# untitled.net
KiCad netlist of a schematic drawn in EAGLE
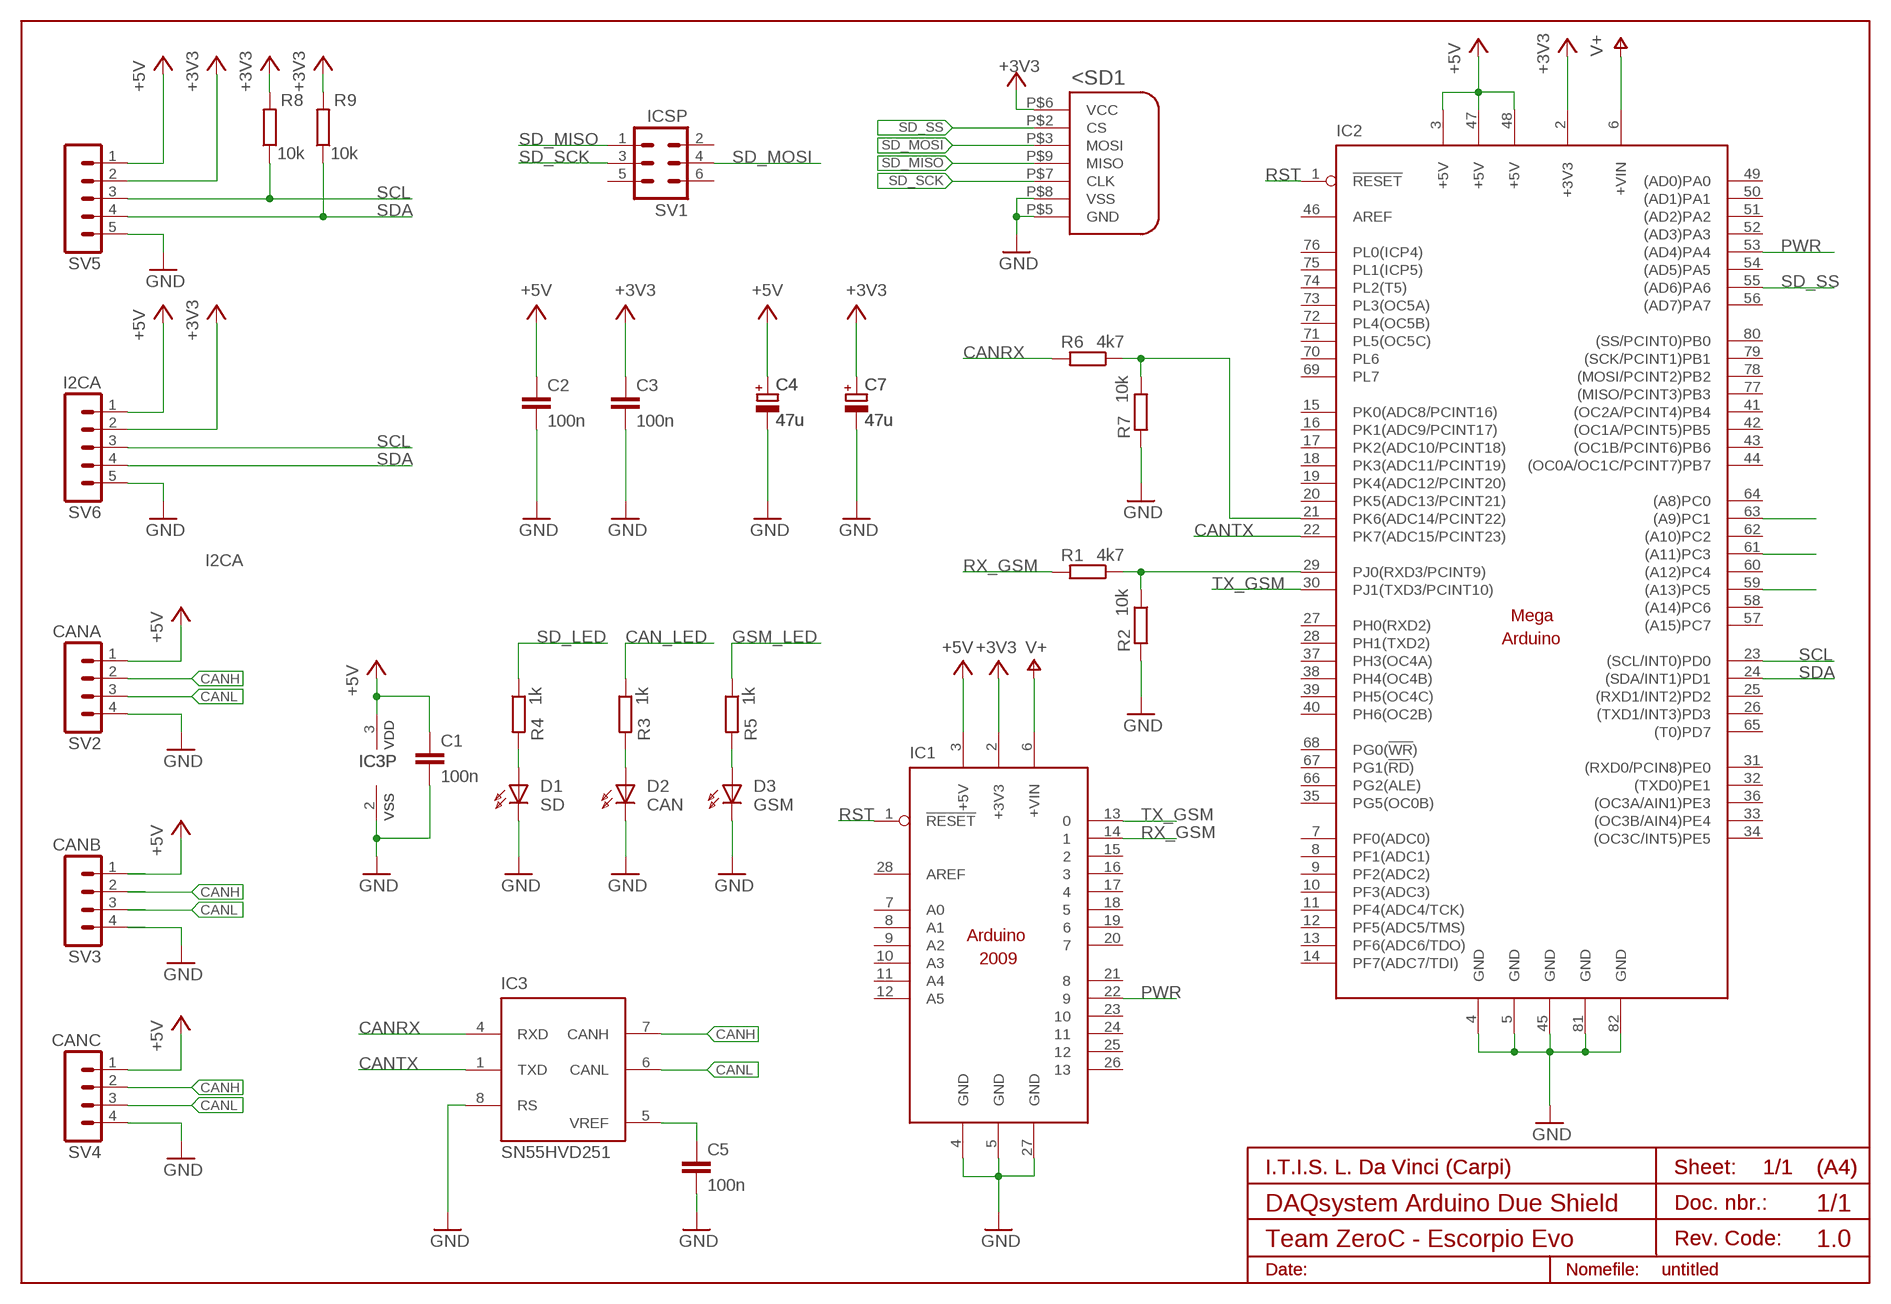
[diagram p0: schematic, sheet 1]

(export (version "E")
  (design (tool "Eeschema 10.0.6"))
  (components
    (comp (ref "C1")
      (value "100n")
      (footprint "eagle-import:C3225")
      (libsource (lib "eagle-import") (part "C-EUC3225"))
    )
    (comp (ref "C2")
      (value "100n")
      (footprint "eagle-import:C3225")
      (libsource (lib "eagle-import") (part "C-EUC3225"))
    )
    (comp (ref "C3")
      (value "100n")
      (footprint "eagle-import:C3225")
      (libsource (lib "eagle-import") (part "C-EUC3225"))
    )
    (comp (ref "C4")
      (value "47u")
      (footprint "eagle-import:E-01")
      (libsource (lib "eagle-import") (part "C_POL_01"))
    )
    (comp (ref "C5")
      (value "100n")
      (footprint "eagle-import:C3225")
      (libsource (lib "eagle-import") (part "C-EUC3225"))
    )
    (comp (ref "C7")
      (value "47u")
      (footprint "eagle-import:E-01")
      (libsource (lib "eagle-import") (part "C_POL_01"))
    )
    (comp (ref "D1")
      (value "SD")
      (footprint "eagle-import:LED5MM")
      (libsource (lib "eagle-import") (part "LED5MM"))
    )
    (comp (ref "D2")
      (value "CAN")
      (footprint "eagle-import:LED5MM")
      (libsource (lib "eagle-import") (part "LED5MM"))
    )
    (comp (ref "D3")
      (value "GSM")
      (footprint "eagle-import:LED5MM")
      (libsource (lib "eagle-import") (part "LED5MM"))
    )
    (comp (ref "IC1")
      (value "ARDUINO2009_10")
      (footprint "eagle-import:ARDUINO2009")
      (libsource (lib "eagle-import") (part "ARDUINO2009_10"))
    )
    (comp (ref "IC2")
      (value "MEGAARDUINO_1")
      (footprint "eagle-import:MEGA_ARDUINO")
      (libsource (lib "eagle-import") (part "MEGAARDUINO_1"))
    )
    (comp (ref "IC3")
      (value "SN55HVD251")
      (footprint "eagle-import:DIL8")
      (libsource (lib "eagle-import") (part "SN55HVD251"))
    )
    (comp (ref "R1")
      (value "4k7")
      (footprint "eagle-import:M1206")
      (libsource (lib "eagle-import") (part "R-EU_M1206"))
    )
    (comp (ref "R2")
      (value "10k")
      (footprint "eagle-import:M1206")
      (libsource (lib "eagle-import") (part "R-EU_M1206"))
    )
    (comp (ref "R3")
      (value "1k")
      (footprint "eagle-import:M1206")
      (libsource (lib "eagle-import") (part "R-EU_M1206"))
    )
    (comp (ref "R4")
      (value "1k")
      (footprint "eagle-import:M1206")
      (libsource (lib "eagle-import") (part "R-EU_M1206"))
    )
    (comp (ref "R5")
      (value "1k")
      (footprint "eagle-import:M1206")
      (libsource (lib "eagle-import") (part "R-EU_M1206"))
    )
    (comp (ref "R6")
      (value "4k7")
      (footprint "eagle-import:M1206")
      (libsource (lib "eagle-import") (part "R-EU_M1206"))
    )
    (comp (ref "R7")
      (value "10k")
      (footprint "eagle-import:M1206")
      (libsource (lib "eagle-import") (part "R-EU_M1206"))
    )
    (comp (ref "R8")
      (value "10k")
      (footprint "eagle-import:M1206")
      (libsource (lib "eagle-import") (part "R-EU_M1206"))
    )
    (comp (ref "R9")
      (value "10k")
      (footprint "eagle-import:M1206")
      (libsource (lib "eagle-import") (part "R-EU_M1206"))
    )
    (comp (ref "SV1")
      (value "ICSP")
      (footprint "eagle-import:MA03-2")
      (libsource (lib "eagle-import") (part "MA03-2"))
    )
    (comp (ref "SV2")
      (value "CANA")
      (footprint "eagle-import:MA04-1")
      (libsource (lib "eagle-import") (part "MA04-1"))
    )
    (comp (ref "SV3")
      (value "CANB")
      (footprint "eagle-import:MA04-1")
      (fields (field (name "OC_FARNELL") "unknown") (field (name "OC_NEWARK") "unknown"))
      (libsource (lib "eagle-import") (part "MA04-1"))
    )
    (comp (ref "SV4")
      (value "CANC")
      (footprint "eagle-import:MA04-1")
      (fields (field (name "OC_FARNELL") "unknown") (field (name "OC_NEWARK") "unknown"))
      (libsource (lib "eagle-import") (part "MA04-1"))
    )
    (comp (ref "SV5")
      (value "I2CA")
      (footprint "eagle-import:MA05-1")
      (libsource (lib "eagle-import") (part "MA05-1"))
    )
    (comp (ref "SV6")
      (value "I2CA")
      (footprint "eagle-import:MA05-1")
      (libsource (lib "eagle-import") (part "MA05-1"))
    )
    (comp (ref "U$2")
      (value "SD_CARD")
      (footprint "eagle-import:SD")
      (libsource (lib "eagle-import") (part "SD_CARD"))
    )
  )
  (nets
    (net (code "1") (name "+3V3") (class "Default")
      (node (ref "C3") (pin "1") (pinfunction "1_1") (pintype "passive"))
      (node (ref "C7") (pin "+") (pinfunction "+_+") (pintype "passive"))
      (node (ref "IC1") (pin "2") (pinfunction "+3V3_2") (pintype "power_in"))
      (node (ref "IC2") (pin "2") (pinfunction "+3V3_2") (pintype "power_in"))
      (node (ref "R8") (pin "2") (pinfunction "2_2") (pintype "passive"))
      (node (ref "R9") (pin "2") (pinfunction "2_2") (pintype "passive"))
      (node (ref "SV5") (pin "2") (pinfunction "2_2") (pintype "passive"))
      (node (ref "SV6") (pin "2") (pinfunction "2_2") (pintype "passive"))
      (node (ref "U$2") (pin "P$6") (pinfunction "VCC_P$6") (pintype "bidirectional"))
    )
    (net (code "2") (name "+5V") (class "Default")
      (node (ref "C1") (pin "1") (pinfunction "1_1") (pintype "passive"))
      (node (ref "C2") (pin "1") (pinfunction "1_1") (pintype "passive"))
      (node (ref "C4") (pin "+") (pinfunction "+_+") (pintype "passive"))
      (node (ref "IC1") (pin "3") (pinfunction "+5V_3") (pintype "power_in"))
      (node (ref "IC2") (pin "3") (pinfunction "+5V_3") (pintype "power_in"))
      (node (ref "IC2") (pin "47") (pinfunction "+5V_47") (pintype "power_in"))
      (node (ref "IC2") (pin "48") (pinfunction "+5V_48") (pintype "power_in"))
      (node (ref "IC3") (pin "3") (pinfunction "VDD_3") (pintype "power_in"))
      (node (ref "SV2") (pin "1") (pinfunction "1_1") (pintype "passive"))
      (node (ref "SV3") (pin "1") (pinfunction "1_1") (pintype "passive"))
      (node (ref "SV4") (pin "1") (pinfunction "1_1") (pintype "passive"))
      (node (ref "SV5") (pin "1") (pinfunction "1_1") (pintype "passive"))
      (node (ref "SV6") (pin "1") (pinfunction "1_1") (pintype "passive"))
    )
    (net (code "3") (name "/CANH") (class "Default")
      (node (ref "IC3") (pin "7") (pinfunction "CANH_7") (pintype "bidirectional"))
      (node (ref "SV2") (pin "2") (pinfunction "2_2") (pintype "passive"))
      (node (ref "SV3") (pin "2") (pinfunction "2_2") (pintype "passive"))
      (node (ref "SV4") (pin "2") (pinfunction "2_2") (pintype "passive"))
    )
    (net (code "4") (name "/CANL") (class "Default")
      (node (ref "IC3") (pin "6") (pinfunction "CANL_6") (pintype "bidirectional"))
      (node (ref "SV2") (pin "3") (pinfunction "3_3") (pintype "passive"))
      (node (ref "SV3") (pin "3") (pinfunction "3_3") (pintype "passive"))
      (node (ref "SV4") (pin "3") (pinfunction "3_3") (pintype "passive"))
    )
    (net (code "5") (name "/CANRX") (class "Default")
      (node (ref "IC3") (pin "4") (pinfunction "RXD_4") (pintype "output"))
      (node (ref "R6") (pin "2") (pinfunction "2_2") (pintype "passive"))
    )
    (net (code "6") (name "/CANTX") (class "Default")
      (node (ref "IC2") (pin "22") (pinfunction "PK7(ADC15/PCINT23)_22") (pintype "bidirectional"))
      (node (ref "IC3") (pin "1") (pinfunction "TXD_1") (pintype "input"))
    )
    (net (code "7") (name "/CAN_LED") (class "Default")
      (node (ref "IC2") (pin "63") (pinfunction "(A9)PC1_63") (pintype "bidirectional"))
      (node (ref "R3") (pin "1") (pinfunction "1_1") (pintype "passive"))
    )
    (net (code "8") (name "/GSM_LED") (class "Default")
      (node (ref "IC2") (pin "61") (pinfunction "(A11)PC3_61") (pintype "bidirectional"))
      (node (ref "R5") (pin "1") (pinfunction "1_1") (pintype "passive"))
    )
    (net (code "9") (name "/PWR") (class "Default")
      (node (ref "IC1") (pin "22") (pinfunction "9_22") (pintype "bidirectional"))
      (node (ref "IC2") (pin "53") (pinfunction "(AD4)PA4_53") (pintype "bidirectional"))
    )
    (net (code "10") (name "/RST") (class "Default")
      (node (ref "IC1") (pin "1") (pinfunction "~{RESET}_1") (pintype "bidirectional"))
      (node (ref "IC2") (pin "1") (pinfunction "~{RESET}_1") (pintype "bidirectional"))
    )
    (net (code "11") (name "/RX_GSM") (class "Default")
      (node (ref "IC1") (pin "14") (pinfunction "1_14") (pintype "bidirectional"))
      (node (ref "R1") (pin "2") (pinfunction "2_2") (pintype "passive"))
    )
    (net (code "12") (name "/SCL") (class "Default")
      (node (ref "IC2") (pin "23") (pinfunction "(SCL/INT0)PD0_23") (pintype "bidirectional"))
      (node (ref "R8") (pin "1") (pinfunction "1_1") (pintype "passive"))
      (node (ref "SV5") (pin "3") (pinfunction "3_3") (pintype "passive"))
      (node (ref "SV6") (pin "3") (pinfunction "3_3") (pintype "passive"))
    )
    (net (code "13") (name "/SDA") (class "Default")
      (node (ref "IC2") (pin "24") (pinfunction "(SDA/INT1)PD1_24") (pintype "bidirectional"))
      (node (ref "R9") (pin "1") (pinfunction "1_1") (pintype "passive"))
      (node (ref "SV5") (pin "4") (pinfunction "4_4") (pintype "passive"))
      (node (ref "SV6") (pin "4") (pinfunction "4_4") (pintype "passive"))
    )
    (net (code "14") (name "/SD_LED") (class "Default")
      (node (ref "IC2") (pin "59") (pinfunction "(A13)PC5_59") (pintype "bidirectional"))
      (node (ref "R4") (pin "1") (pinfunction "1_1") (pintype "passive"))
    )
    (net (code "15") (name "/SD_MISO") (class "Default")
      (node (ref "SV1") (pin "1") (pinfunction "1_1") (pintype "passive"))
      (node (ref "U$2") (pin "P$9") (pinfunction "MISO_P$9") (pintype "bidirectional"))
    )
    (net (code "16") (name "/SD_MOSI") (class "Default")
      (node (ref "SV1") (pin "4") (pinfunction "4_4") (pintype "passive"))
      (node (ref "U$2") (pin "P$3") (pinfunction "MOSI_P$3") (pintype "bidirectional"))
    )
    (net (code "17") (name "/SD_SCK") (class "Default")
      (node (ref "SV1") (pin "3") (pinfunction "3_3") (pintype "passive"))
      (node (ref "U$2") (pin "P$7") (pinfunction "CLK_P$7") (pintype "bidirectional"))
    )
    (net (code "18") (name "/SD_SS") (class "Default")
      (node (ref "IC2") (pin "55") (pinfunction "(AD6)PA6_55") (pintype "bidirectional"))
      (node (ref "U$2") (pin "P$2") (pinfunction "CS_P$2") (pintype "bidirectional"))
    )
    (net (code "19") (name "/TX_GSM") (class "Default")
      (node (ref "IC1") (pin "13") (pinfunction "0_13") (pintype "bidirectional"))
      (node (ref "IC2") (pin "30") (pinfunction "PJ1(TXD3/PCINT10)_30") (pintype "bidirectional"))
    )
    (net (code "20") (name "GND") (class "Default")
      (node (ref "C1") (pin "2") (pinfunction "2_2") (pintype "passive"))
      (node (ref "C2") (pin "2") (pinfunction "2_2") (pintype "passive"))
      (node (ref "C3") (pin "2") (pinfunction "2_2") (pintype "passive"))
      (node (ref "C4") (pin "-") (pinfunction "-_-") (pintype "passive"))
      (node (ref "C5") (pin "2") (pinfunction "2_2") (pintype "passive"))
      (node (ref "C7") (pin "-") (pinfunction "-_-") (pintype "passive"))
      (node (ref "D1") (pin "K") (pinfunction "C_K") (pintype "passive"))
      (node (ref "D2") (pin "K") (pinfunction "C_K") (pintype "passive"))
      (node (ref "D3") (pin "K") (pinfunction "C_K") (pintype "passive"))
      (node (ref "IC1") (pin "27") (pinfunction "GND_27") (pintype "power_in"))
      (node (ref "IC1") (pin "4") (pinfunction "GND_4") (pintype "power_in"))
      (node (ref "IC1") (pin "5") (pinfunction "GND_5") (pintype "power_in"))
      (node (ref "IC2") (pin "4") (pinfunction "GND_4") (pintype "power_in"))
      (node (ref "IC2") (pin "45") (pinfunction "GND_45") (pintype "power_in"))
      (node (ref "IC2") (pin "5") (pinfunction "GND_5") (pintype "power_in"))
      (node (ref "IC2") (pin "81") (pinfunction "GND_81") (pintype "power_in"))
      (node (ref "IC2") (pin "82") (pinfunction "GND_82") (pintype "power_in"))
      (node (ref "IC3") (pin "2") (pinfunction "VSS_2") (pintype "power_in"))
      (node (ref "IC3") (pin "8") (pinfunction "RS_8") (pintype "input"))
      (node (ref "R2") (pin "2") (pinfunction "2_2") (pintype "passive"))
      (node (ref "R7") (pin "2") (pinfunction "2_2") (pintype "passive"))
      (node (ref "SV2") (pin "4") (pinfunction "4_4") (pintype "passive"))
      (node (ref "SV3") (pin "4") (pinfunction "4_4") (pintype "passive"))
      (node (ref "SV4") (pin "4") (pinfunction "4_4") (pintype "passive"))
      (node (ref "SV5") (pin "5") (pinfunction "5_5") (pintype "passive"))
      (node (ref "SV6") (pin "5") (pinfunction "5_5") (pintype "passive"))
      (node (ref "U$2") (pin "P$5") (pinfunction "GND_P$5") (pintype "bidirectional"))
      (node (ref "U$2") (pin "P$8") (pinfunction "VSS_P$8") (pintype "bidirectional"))
    )
    (net (code "21") (name "Net-(D1-PadA)") (class "Default")
      (node (ref "D1") (pin "A") (pinfunction "A_A") (pintype "passive"))
      (node (ref "R4") (pin "2") (pinfunction "2_2") (pintype "passive"))
    )
    (net (code "22") (name "Net-(D2-PadA)") (class "Default")
      (node (ref "D2") (pin "A") (pinfunction "A_A") (pintype "passive"))
      (node (ref "R3") (pin "2") (pinfunction "2_2") (pintype "passive"))
    )
    (net (code "23") (name "Net-(D3-PadA)") (class "Default")
      (node (ref "D3") (pin "A") (pinfunction "A_A") (pintype "passive"))
      (node (ref "R5") (pin "2") (pinfunction "2_2") (pintype "passive"))
    )
    (net (code "24") (name "Net-(IC2-PJ0(RXD3{slash}PCINT9))") (class "Default")
      (node (ref "IC2") (pin "29") (pinfunction "PJ0(RXD3/PCINT9)_29") (pintype "bidirectional"))
      (node (ref "R1") (pin "1") (pinfunction "1_1") (pintype "passive"))
      (node (ref "R2") (pin "1") (pinfunction "1_1") (pintype "passive"))
    )
    (net (code "25") (name "Net-(IC2-PK6(ADC14{slash}PCINT22))") (class "Default")
      (node (ref "IC2") (pin "21") (pinfunction "PK6(ADC14/PCINT22)_21") (pintype "bidirectional"))
      (node (ref "R6") (pin "1") (pinfunction "1_1") (pintype "passive"))
      (node (ref "R7") (pin "1") (pinfunction "1_1") (pintype "passive"))
    )
    (net (code "26") (name "Net-(IC3A-VREF)") (class "Default")
      (node (ref "C5") (pin "1") (pinfunction "1_1") (pintype "passive"))
      (node (ref "IC3") (pin "5") (pinfunction "VREF_5") (pintype "power_in"))
    )
    (net (code "27") (name "V+") (class "Default")
      (node (ref "IC1") (pin "6") (pinfunction "+VIN_6") (pintype "bidirectional"))
      (node (ref "IC2") (pin "6") (pinfunction "+VIN_6") (pintype "power_in"))
    )
    (net (code "28") (name "unconnected-(IC1-2-Pad15)") (class "Default")
      (node (ref "IC1") (pin "15") (pinfunction "2_15") (pintype "bidirectional"))
    )
    (net (code "29") (name "unconnected-(IC1-3-Pad16)") (class "Default")
      (node (ref "IC1") (pin "16") (pinfunction "3_16") (pintype "bidirectional"))
    )
    (net (code "30") (name "unconnected-(IC1-4-Pad17)") (class "Default")
      (node (ref "IC1") (pin "17") (pinfunction "4_17") (pintype "bidirectional"))
    )
    (net (code "31") (name "unconnected-(IC1-5-Pad18)") (class "Default")
      (node (ref "IC1") (pin "18") (pinfunction "5_18") (pintype "bidirectional"))
    )
    (net (code "32") (name "unconnected-(IC1-6-Pad19)") (class "Default")
      (node (ref "IC1") (pin "19") (pinfunction "6_19") (pintype "bidirectional"))
    )
    (net (code "33") (name "unconnected-(IC1-7-Pad20)") (class "Default")
      (node (ref "IC1") (pin "20") (pinfunction "7_20") (pintype "bidirectional"))
    )
    (net (code "34") (name "unconnected-(IC1-8-Pad21)") (class "Default")
      (node (ref "IC1") (pin "21") (pinfunction "8_21") (pintype "bidirectional"))
    )
    (net (code "35") (name "unconnected-(IC1-10-Pad23)") (class "Default")
      (node (ref "IC1") (pin "23") (pinfunction "10_23") (pintype "bidirectional"))
    )
    (net (code "36") (name "unconnected-(IC1-11-Pad24)") (class "Default")
      (node (ref "IC1") (pin "24") (pinfunction "11_24") (pintype "bidirectional"))
    )
    (net (code "37") (name "unconnected-(IC1-12-Pad25)") (class "Default")
      (node (ref "IC1") (pin "25") (pinfunction "12_25") (pintype "bidirectional"))
    )
    (net (code "38") (name "unconnected-(IC1-13-Pad26)") (class "Default")
      (node (ref "IC1") (pin "26") (pinfunction "13_26") (pintype "bidirectional"))
    )
    (net (code "39") (name "unconnected-(IC1-A0-Pad7)") (class "Default")
      (node (ref "IC1") (pin "7") (pinfunction "A0_7") (pintype "bidirectional"))
    )
    (net (code "40") (name "unconnected-(IC1-A1-Pad8)") (class "Default")
      (node (ref "IC1") (pin "8") (pinfunction "A1_8") (pintype "bidirectional"))
    )
    (net (code "41") (name "unconnected-(IC1-A2-Pad9)") (class "Default")
      (node (ref "IC1") (pin "9") (pinfunction "A2_9") (pintype "bidirectional"))
    )
    (net (code "42") (name "unconnected-(IC1-A3-Pad10)") (class "Default")
      (node (ref "IC1") (pin "10") (pinfunction "A3_10") (pintype "bidirectional"))
    )
    (net (code "43") (name "unconnected-(IC1-A4-Pad11)") (class "Default")
      (node (ref "IC1") (pin "11") (pinfunction "A4_11") (pintype "bidirectional"))
    )
    (net (code "44") (name "unconnected-(IC1-A5-Pad12)") (class "Default")
      (node (ref "IC1") (pin "12") (pinfunction "A5_12") (pintype "bidirectional"))
    )
    (net (code "45") (name "unconnected-(IC1-AREF-Pad28)") (class "Default")
      (node (ref "IC1") (pin "28") (pinfunction "AREF_28") (pintype "bidirectional"))
    )
    (net (code "46") (name "unconnected-(IC2-(A8)PC0-Pad64)") (class "Default")
      (node (ref "IC2") (pin "64") (pinfunction "(A8)PC0_64") (pintype "bidirectional"))
    )
    (net (code "47") (name "unconnected-(IC2-(A10)PC2-Pad62)") (class "Default")
      (node (ref "IC2") (pin "62") (pinfunction "(A10)PC2_62") (pintype "bidirectional"))
    )
    (net (code "48") (name "unconnected-(IC2-(A12)PC4-Pad60)") (class "Default")
      (node (ref "IC2") (pin "60") (pinfunction "(A12)PC4_60") (pintype "bidirectional"))
    )
    (net (code "49") (name "unconnected-(IC2-(A14)PC6-Pad58)") (class "Default")
      (node (ref "IC2") (pin "58") (pinfunction "(A14)PC6_58") (pintype "bidirectional"))
    )
    (net (code "50") (name "unconnected-(IC2-(A15)PC7-Pad57)") (class "Default")
      (node (ref "IC2") (pin "57") (pinfunction "(A15)PC7_57") (pintype "bidirectional"))
    )
    (net (code "51") (name "unconnected-(IC2-(AD0)PA0-Pad49)") (class "Default")
      (node (ref "IC2") (pin "49") (pinfunction "(AD0)PA0_49") (pintype "bidirectional"))
    )
    (net (code "52") (name "unconnected-(IC2-(AD1)PA1-Pad50)") (class "Default")
      (node (ref "IC2") (pin "50") (pinfunction "(AD1)PA1_50") (pintype "bidirectional"))
    )
    (net (code "53") (name "unconnected-(IC2-(AD2)PA2-Pad51)") (class "Default")
      (node (ref "IC2") (pin "51") (pinfunction "(AD2)PA2_51") (pintype "bidirectional"))
    )
    (net (code "54") (name "unconnected-(IC2-(AD3)PA3-Pad52)") (class "Default")
      (node (ref "IC2") (pin "52") (pinfunction "(AD3)PA3_52") (pintype "bidirectional"))
    )
    (net (code "55") (name "unconnected-(IC2-(AD5)PA5-Pad54)") (class "Default")
      (node (ref "IC2") (pin "54") (pinfunction "(AD5)PA5_54") (pintype "bidirectional"))
    )
    (net (code "56") (name "unconnected-(IC2-(AD7)PA7-Pad56)") (class "Default")
      (node (ref "IC2") (pin "56") (pinfunction "(AD7)PA7_56") (pintype "bidirectional"))
    )
    (net (code "57") (name "unconnected-(IC2-(MISO{slash}PCINT3)PB3-Pad77)") (class "Default")
      (node (ref "IC2") (pin "77") (pinfunction "(MISO/PCINT3)PB3_77") (pintype "bidirectional"))
    )
    (net (code "58") (name "unconnected-(IC2-(MOSI{slash}PCINT2)PB2-Pad78)") (class "Default")
      (node (ref "IC2") (pin "78") (pinfunction "(MOSI/PCINT2)PB2_78") (pintype "bidirectional"))
    )
    (net (code "59") (name "unconnected-(IC2-(OC0A{slash}OC1C{slash}PCINT7)PB7-Pad44)") (class "Default")
      (node (ref "IC2") (pin "44") (pinfunction "(OC0A/OC1C/PCINT7)PB7_44") (pintype "bidirectional"))
    )
    (net (code "60") (name "unconnected-(IC2-(OC1A{slash}PCINT5)PB5-Pad42)") (class "Default")
      (node (ref "IC2") (pin "42") (pinfunction "(OC1A/PCINT5)PB5_42") (pintype "bidirectional"))
    )
    (net (code "61") (name "unconnected-(IC2-(OC1B{slash}PCINT6)PB6-Pad43)") (class "Default")
      (node (ref "IC2") (pin "43") (pinfunction "(OC1B/PCINT6)PB6_43") (pintype "bidirectional"))
    )
    (net (code "62") (name "unconnected-(IC2-(OC2A{slash}PCINT4)PB4-Pad41)") (class "Default")
      (node (ref "IC2") (pin "41") (pinfunction "(OC2A/PCINT4)PB4_41") (pintype "bidirectional"))
    )
    (net (code "63") (name "unconnected-(IC2-(OC3A{slash}AIN1)PE3-Pad36)") (class "Default")
      (node (ref "IC2") (pin "36") (pinfunction "(OC3A/AIN1)PE3_36") (pintype "bidirectional"))
    )
    (net (code "64") (name "unconnected-(IC2-(OC3B{slash}AIN4)PE4-Pad33)") (class "Default")
      (node (ref "IC2") (pin "33") (pinfunction "(OC3B/AIN4)PE4_33") (pintype "bidirectional"))
    )
    (net (code "65") (name "unconnected-(IC2-(OC3C{slash}INT5)PE5-Pad34)") (class "Default")
      (node (ref "IC2") (pin "34") (pinfunction "(OC3C/INT5)PE5_34") (pintype "bidirectional"))
    )
    (net (code "66") (name "unconnected-(IC2-(RXD0{slash}PCIN8)PE0-Pad31)") (class "Default")
      (node (ref "IC2") (pin "31") (pinfunction "(RXD0/PCIN8)PE0_31") (pintype "bidirectional"))
    )
    (net (code "67") (name "unconnected-(IC2-(RXD1{slash}INT2)PD2-Pad25)") (class "Default")
      (node (ref "IC2") (pin "25") (pinfunction "(RXD1/INT2)PD2_25") (pintype "bidirectional"))
    )
    (net (code "68") (name "unconnected-(IC2-(SCK{slash}PCINT1)PB1-Pad79)") (class "Default")
      (node (ref "IC2") (pin "79") (pinfunction "(SCK/PCINT1)PB1_79") (pintype "bidirectional"))
    )
    (net (code "69") (name "unconnected-(IC2-(SS{slash}PCINT0)PB0-Pad80)") (class "Default")
      (node (ref "IC2") (pin "80") (pinfunction "(SS/PCINT0)PB0_80") (pintype "bidirectional"))
    )
    (net (code "70") (name "unconnected-(IC2-(T0)PD7-Pad65)") (class "Default")
      (node (ref "IC2") (pin "65") (pinfunction "(T0)PD7_65") (pintype "bidirectional"))
    )
    (net (code "71") (name "unconnected-(IC2-(TXD0)PE1-Pad32)") (class "Default")
      (node (ref "IC2") (pin "32") (pinfunction "(TXD0)PE1_32") (pintype "bidirectional"))
    )
    (net (code "72") (name "unconnected-(IC2-(TXD1{slash}INT3)PD3-Pad26)") (class "Default")
      (node (ref "IC2") (pin "26") (pinfunction "(TXD1/INT3)PD3_26") (pintype "bidirectional"))
    )
    (net (code "73") (name "unconnected-(IC2-AREF-Pad46)") (class "Default")
      (node (ref "IC2") (pin "46") (pinfunction "AREF_46") (pintype "bidirectional"))
    )
    (net (code "74") (name "unconnected-(IC2-PF0(ADC0)-Pad7)") (class "Default")
      (node (ref "IC2") (pin "7") (pinfunction "PF0(ADC0)_7") (pintype "bidirectional"))
    )
    (net (code "75") (name "unconnected-(IC2-PF1(ADC1)-Pad8)") (class "Default")
      (node (ref "IC2") (pin "8") (pinfunction "PF1(ADC1)_8") (pintype "bidirectional"))
    )
    (net (code "76") (name "unconnected-(IC2-PF2(ADC2)-Pad9)") (class "Default")
      (node (ref "IC2") (pin "9") (pinfunction "PF2(ADC2)_9") (pintype "bidirectional"))
    )
    (net (code "77") (name "unconnected-(IC2-PF3(ADC3)-Pad10)") (class "Default")
      (node (ref "IC2") (pin "10") (pinfunction "PF3(ADC3)_10") (pintype "bidirectional"))
    )
    (net (code "78") (name "unconnected-(IC2-PF4(ADC4{slash}TCK)-Pad11)") (class "Default")
      (node (ref "IC2") (pin "11") (pinfunction "PF4(ADC4/TCK)_11") (pintype "bidirectional"))
    )
    (net (code "79") (name "unconnected-(IC2-PF5(ADC5{slash}TMS)-Pad12)") (class "Default")
      (node (ref "IC2") (pin "12") (pinfunction "PF5(ADC5/TMS)_12") (pintype "bidirectional"))
    )
    (net (code "80") (name "unconnected-(IC2-PF6(ADC6{slash}TDO)-Pad13)") (class "Default")
      (node (ref "IC2") (pin "13") (pinfunction "PF6(ADC6/TDO)_13") (pintype "bidirectional"))
    )
    (net (code "81") (name "unconnected-(IC2-PF7(ADC7{slash}TDI)-Pad14)") (class "Default")
      (node (ref "IC2") (pin "14") (pinfunction "PF7(ADC7/TDI)_14") (pintype "bidirectional"))
    )
    (net (code "82") (name "unconnected-(IC2-PG0(~{WR})-Pad68)") (class "Default")
      (node (ref "IC2") (pin "68") (pinfunction "PG0(~{WR})_68") (pintype "bidirectional"))
    )
    (net (code "83") (name "unconnected-(IC2-PG1(~{RD})-Pad67)") (class "Default")
      (node (ref "IC2") (pin "67") (pinfunction "PG1(~{RD})_67") (pintype "bidirectional"))
    )
    (net (code "84") (name "unconnected-(IC2-PG2(ALE)-Pad66)") (class "Default")
      (node (ref "IC2") (pin "66") (pinfunction "PG2(ALE)_66") (pintype "bidirectional"))
    )
    (net (code "85") (name "unconnected-(IC2-PG5(OC0B)-Pad35)") (class "Default")
      (node (ref "IC2") (pin "35") (pinfunction "PG5(OC0B)_35") (pintype "bidirectional"))
    )
    (net (code "86") (name "unconnected-(IC2-PH0(RXD2)-Pad27)") (class "Default")
      (node (ref "IC2") (pin "27") (pinfunction "PH0(RXD2)_27") (pintype "bidirectional"))
    )
    (net (code "87") (name "unconnected-(IC2-PH1(TXD2)-Pad28)") (class "Default")
      (node (ref "IC2") (pin "28") (pinfunction "PH1(TXD2)_28") (pintype "bidirectional"))
    )
    (net (code "88") (name "unconnected-(IC2-PH3(OC4A)-Pad37)") (class "Default")
      (node (ref "IC2") (pin "37") (pinfunction "PH3(OC4A)_37") (pintype "bidirectional"))
    )
    (net (code "89") (name "unconnected-(IC2-PH4(OC4B)-Pad38)") (class "Default")
      (node (ref "IC2") (pin "38") (pinfunction "PH4(OC4B)_38") (pintype "bidirectional"))
    )
    (net (code "90") (name "unconnected-(IC2-PH5(OC4C)-Pad39)") (class "Default")
      (node (ref "IC2") (pin "39") (pinfunction "PH5(OC4C)_39") (pintype "bidirectional"))
    )
    (net (code "91") (name "unconnected-(IC2-PH6(OC2B)-Pad40)") (class "Default")
      (node (ref "IC2") (pin "40") (pinfunction "PH6(OC2B)_40") (pintype "bidirectional"))
    )
    (net (code "92") (name "unconnected-(IC2-PK0(ADC8{slash}PCINT16)-Pad15)") (class "Default")
      (node (ref "IC2") (pin "15") (pinfunction "PK0(ADC8/PCINT16)_15") (pintype "bidirectional"))
    )
    (net (code "93") (name "unconnected-(IC2-PK1(ADC9{slash}PCINT17)-Pad16)") (class "Default")
      (node (ref "IC2") (pin "16") (pinfunction "PK1(ADC9/PCINT17)_16") (pintype "bidirectional"))
    )
    (net (code "94") (name "unconnected-(IC2-PK2(ADC10{slash}PCINT18)-Pad17)") (class "Default")
      (node (ref "IC2") (pin "17") (pinfunction "PK2(ADC10/PCINT18)_17") (pintype "bidirectional"))
    )
    (net (code "95") (name "unconnected-(IC2-PK3(ADC11{slash}PCINT19)-Pad18)") (class "Default")
      (node (ref "IC2") (pin "18") (pinfunction "PK3(ADC11/PCINT19)_18") (pintype "bidirectional"))
    )
    (net (code "96") (name "unconnected-(IC2-PK4(ADC12{slash}PCINT20)-Pad19)") (class "Default")
      (node (ref "IC2") (pin "19") (pinfunction "PK4(ADC12/PCINT20)_19") (pintype "bidirectional"))
    )
    (net (code "97") (name "unconnected-(IC2-PK5(ADC13{slash}PCINT21)-Pad20)") (class "Default")
      (node (ref "IC2") (pin "20") (pinfunction "PK5(ADC13/PCINT21)_20") (pintype "bidirectional"))
    )
    (net (code "98") (name "unconnected-(IC2-PL0(ICP4)-Pad76)") (class "Default")
      (node (ref "IC2") (pin "76") (pinfunction "PL0(ICP4)_76") (pintype "bidirectional"))
    )
    (net (code "99") (name "unconnected-(IC2-PL1(ICP5)-Pad75)") (class "Default")
      (node (ref "IC2") (pin "75") (pinfunction "PL1(ICP5)_75") (pintype "bidirectional"))
    )
    (net (code "100") (name "unconnected-(IC2-PL2(T5)-Pad74)") (class "Default")
      (node (ref "IC2") (pin "74") (pinfunction "PL2(T5)_74") (pintype "bidirectional"))
    )
    (net (code "101") (name "unconnected-(IC2-PL3(OC5A)-Pad73)") (class "Default")
      (node (ref "IC2") (pin "73") (pinfunction "PL3(OC5A)_73") (pintype "bidirectional"))
    )
    (net (code "102") (name "unconnected-(IC2-PL4(OC5B)-Pad72)") (class "Default")
      (node (ref "IC2") (pin "72") (pinfunction "PL4(OC5B)_72") (pintype "bidirectional"))
    )
    (net (code "103") (name "unconnected-(IC2-PL5(OC5C)-Pad71)") (class "Default")
      (node (ref "IC2") (pin "71") (pinfunction "PL5(OC5C)_71") (pintype "bidirectional"))
    )
    (net (code "104") (name "unconnected-(IC2-PL6-Pad70)") (class "Default")
      (node (ref "IC2") (pin "70") (pinfunction "PL6_70") (pintype "bidirectional"))
    )
    (net (code "105") (name "unconnected-(IC2-PL7-Pad69)") (class "Default")
      (node (ref "IC2") (pin "69") (pinfunction "PL7_69") (pintype "bidirectional"))
    )
    (net (code "106") (name "unconnected-(SV1-Pad2)") (class "Default")
      (node (ref "SV1") (pin "2") (pinfunction "2_2") (pintype "passive"))
    )
    (net (code "107") (name "unconnected-(SV1-Pad5)") (class "Default")
      (node (ref "SV1") (pin "5") (pinfunction "5_5") (pintype "passive"))
    )
    (net (code "108") (name "unconnected-(SV1-Pad6)") (class "Default")
      (node (ref "SV1") (pin "6") (pinfunction "6_6") (pintype "passive"))
    )
  )
)
